# Prova01.net
KiCad netlist of a schematic drawn in EAGLE
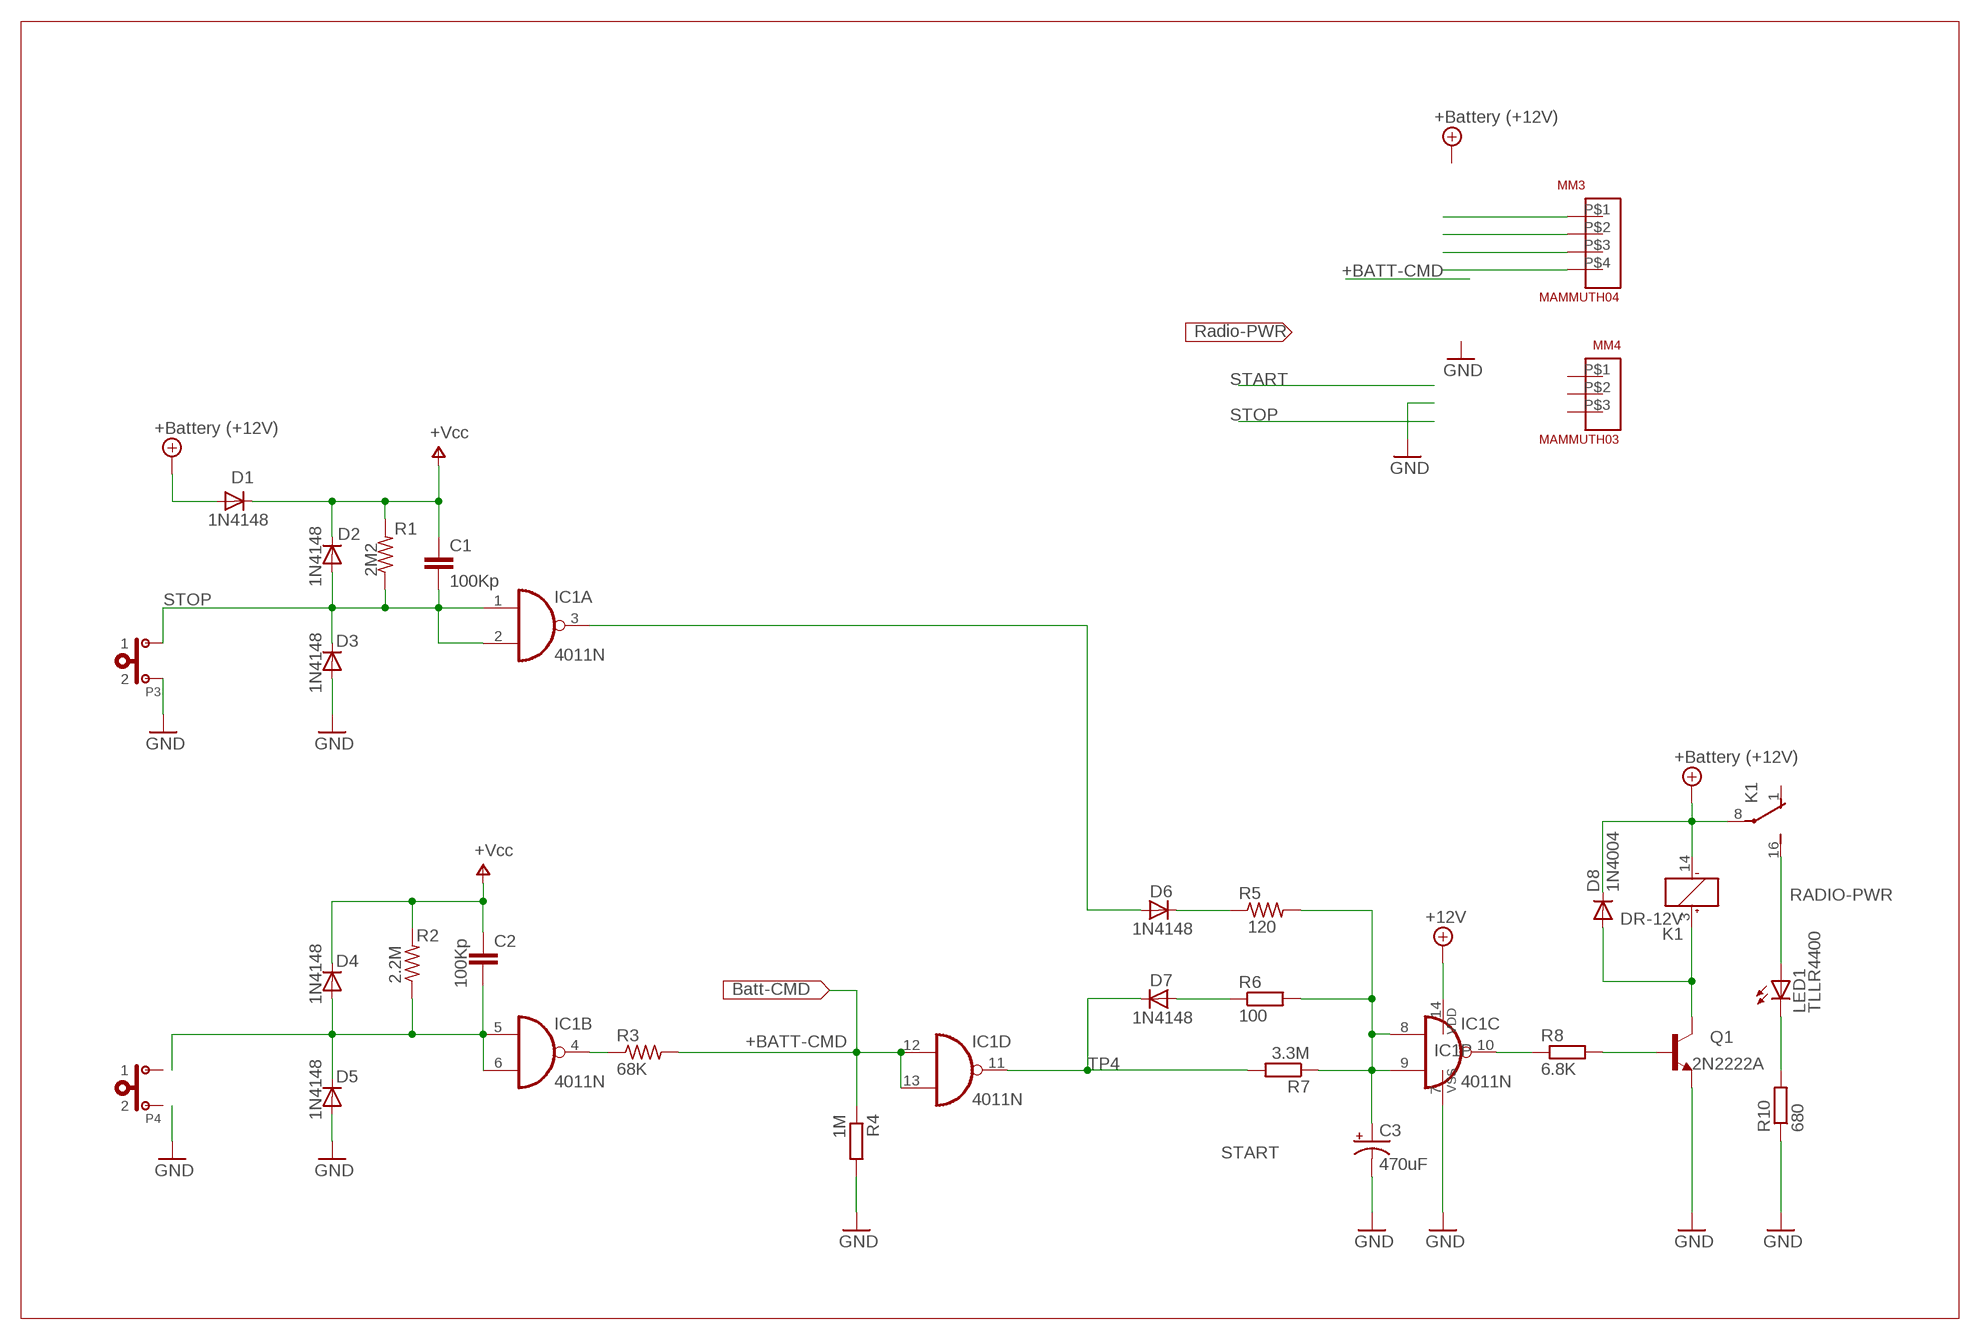
[diagram p0: schematic, sheet 1]

(export (version "E")
  (design (tool "Eeschema 10.0.6"))
  (components
    (comp (ref "C1")
      (value "100Kp")
      (footprint "eagle-import:C025-025X050")
      (libsource (lib "eagle-import") (part "C-EU025-025X050"))
    )
    (comp (ref "C2")
      (value "100Kp")
      (footprint "eagle-import:C025-025X050")
      (libsource (lib "eagle-import") (part "C-EU025-025X050"))
    )
    (comp (ref "C3")
      (value "470uF")
      (footprint "eagle-import:E3,5-8")
      (libsource (lib "eagle-import") (part "CPOL-USE3.5-8"))
    )
    (comp (ref "D1")
      (value "1N4148")
      (footprint "eagle-import:DO35-10")
      (libsource (lib "eagle-import") (part "1N4148DO35-10"))
    )
    (comp (ref "D2")
      (value "1N4148")
      (footprint "eagle-import:DO35-10")
      (libsource (lib "eagle-import") (part "1N4148DO35-10"))
    )
    (comp (ref "D3")
      (value "1N4148")
      (footprint "eagle-import:DO35-10")
      (libsource (lib "eagle-import") (part "1N4148DO35-10"))
    )
    (comp (ref "D4")
      (value "1N4148")
      (footprint "eagle-import:DO35-10")
      (libsource (lib "eagle-import") (part "1N4148DO35-10"))
    )
    (comp (ref "D5")
      (value "1N4148")
      (footprint "eagle-import:DO35-10")
      (libsource (lib "eagle-import") (part "1N4148DO35-10"))
    )
    (comp (ref "D6")
      (value "1N4148")
      (footprint "eagle-import:DO35-10")
      (libsource (lib "eagle-import") (part "1N4148DO35-10"))
    )
    (comp (ref "D7")
      (value "1N4148")
      (footprint "eagle-import:DO35-10")
      (libsource (lib "eagle-import") (part "1N4148DO35-10"))
    )
    (comp (ref "D8")
      (value "1N4004")
      (footprint "eagle-import:DO41-10")
      (libsource (lib "eagle-import") (part "1N4004"))
    )
    (comp (ref "IC1")
      (value "4011N")
      (footprint "eagle-import:DIL14")
      (libsource (lib "eagle-import") (part "4011N"))
    )
    (comp (ref "K1")
      (value "DR-12V")
      (footprint "eagle-import:DR-1")
      (libsource (lib "eagle-import") (part "DR-V12"))
    )
    (comp (ref "LED1")
      (value "TLLR4400")
      (footprint "eagle-import:LED3MM")
      (fields (field (name "MF") "VISHAY SEMICONDUCTOR"))
      (libsource (lib "eagle-import") (part "TLLR4400"))
    )
    (comp (ref "MM3")
      (value "MAMMUTH04")
      (footprint "eagle-import:MAMMUTH04")
      (libsource (lib "eagle-import") (part "MAMMUTH04"))
    )
    (comp (ref "MM4")
      (value "MAMMUTH03")
      (footprint "eagle-import:MAMMUTH03")
      (libsource (lib "eagle-import") (part "MAMMUTH03"))
    )
    (comp (ref "P3")
      (value "PULSANTENO")
      (footprint "eagle-import:SIP02")
      (libsource (lib "eagle-import") (part "PULSANTENO"))
    )
    (comp (ref "P4")
      (value "PULSANTENO")
      (footprint "eagle-import:SIP02")
      (libsource (lib "eagle-import") (part "PULSANTENO"))
    )
    (comp (ref "Q1")
      (value "2N2222A")
      (footprint "eagle-import:TO18")
      (libsource (lib "eagle-import") (part "2N2222A"))
    )
    (comp (ref "R1")
      (value "2M2")
      (footprint "eagle-import:0207_12")
      (libsource (lib "eagle-import") (part "R-US_0207/12"))
    )
    (comp (ref "R2")
      (value "2.2M")
      (footprint "eagle-import:0207_12")
      (libsource (lib "eagle-import") (part "R-US_0207/12"))
    )
    (comp (ref "R3")
      (value "68K")
      (footprint "eagle-import:0207_12")
      (libsource (lib "eagle-import") (part "R-US_0207/12"))
    )
    (comp (ref "R4")
      (value "1M")
      (footprint "eagle-import:0207_10")
      (libsource (lib "eagle-import") (part "R-EU_0207/10"))
    )
    (comp (ref "R5")
      (value "120")
      (footprint "eagle-import:0207_12")
      (libsource (lib "eagle-import") (part "R-US_0207/12"))
    )
    (comp (ref "R6")
      (value "100")
      (footprint "eagle-import:0207_10")
      (libsource (lib "eagle-import") (part "R-EU_0207/10"))
    )
    (comp (ref "R7")
      (value "3.3M")
      (footprint "eagle-import:0207_10")
      (libsource (lib "eagle-import") (part "R-EU_0207/10"))
    )
    (comp (ref "R8")
      (value "6.8K")
      (footprint "eagle-import:0207_10")
      (libsource (lib "eagle-import") (part "R-EU_0207/10"))
    )
    (comp (ref "R10")
      (value "680")
      (footprint "eagle-import:0207_10")
      (libsource (lib "eagle-import") (part "R-EU_0207/10"))
    )
  )
  (nets
    (net (code "1") (name "+12V") (class "Default")
      (node (ref "D1") (pin "A") (pinfunction "A_A") (pintype "passive"))
      (node (ref "D8") (pin "C") (pinfunction "C_C") (pintype "passive"))
      (node (ref "IC1") (pin "14") (pinfunction "VDD_14") (pintype "power_in"))
      (node (ref "K1") (pin "14") (pinfunction "-_14") (pintype "passive"))
      (node (ref "K1") (pin "8") (pinfunction "P_8") (pintype "passive"))
    )
    (net (code "2") (name "+Vcc") (class "Default")
      (node (ref "C1") (pin "1") (pinfunction "1_1") (pintype "passive"))
      (node (ref "C2") (pin "1") (pinfunction "1_1") (pintype "passive"))
      (node (ref "D1") (pin "C") (pinfunction "C_C") (pintype "passive"))
      (node (ref "D2") (pin "C") (pinfunction "C_C") (pintype "passive"))
      (node (ref "D4") (pin "C") (pinfunction "C_C") (pintype "passive"))
      (node (ref "R1") (pin "2") (pinfunction "2_2") (pintype "passive"))
      (node (ref "R2") (pin "2") (pinfunction "2_2") (pintype "passive"))
    )
    (net (code "3") (name "/+BATT-CMD") (class "Default")
      (node (ref "IC1") (pin "12") (pinfunction "I0_12") (pintype "input"))
      (node (ref "IC1") (pin "13") (pinfunction "I1_13") (pintype "input"))
      (node (ref "R3") (pin "2") (pinfunction "2_2") (pintype "passive"))
      (node (ref "R4") (pin "1") (pinfunction "1_1") (pintype "passive"))
    )
    (net (code "4") (name "/RADIO-PWR") (class "Default")
      (node (ref "K1") (pin "16") (pinfunction "S_16") (pintype "passive"))
      (node (ref "LED1") (pin "A") (pinfunction "A_A") (pintype "passive"))
    )
    (net (code "5") (name "/START") (class "Default")
      (node (ref "D7") (pin "A") (pinfunction "A_A") (pintype "passive"))
      (node (ref "R6") (pin "1") (pinfunction "1_1") (pintype "passive"))
    )
    (net (code "6") (name "/STOP") (class "Default")
      (node (ref "C1") (pin "2") (pinfunction "2_2") (pintype "passive"))
      (node (ref "D2") (pin "A") (pinfunction "A_A") (pintype "passive"))
      (node (ref "D3") (pin "C") (pinfunction "C_C") (pintype "passive"))
      (node (ref "IC1") (pin "1") (pinfunction "I0_1") (pintype "input"))
      (node (ref "IC1") (pin "2") (pinfunction "I1_2") (pintype "input"))
      (node (ref "P3") (pin "1") (pinfunction "1_1") (pintype "bidirectional"))
      (node (ref "R1") (pin "1") (pinfunction "1_1") (pintype "passive"))
    )
    (net (code "7") (name "/TP4") (class "Default")
      (node (ref "D7") (pin "C") (pinfunction "C_C") (pintype "passive"))
      (node (ref "IC1") (pin "11") (pinfunction "O_11") (pintype "output"))
      (node (ref "R7") (pin "2") (pinfunction "2_2") (pintype "passive"))
    )
    (net (code "8") (name "GND") (class "Default")
      (node (ref "C3") (pin "-") (pinfunction "-_-") (pintype "passive"))
      (node (ref "D3") (pin "A") (pinfunction "A_A") (pintype "passive"))
      (node (ref "D5") (pin "A") (pinfunction "A_A") (pintype "passive"))
      (node (ref "IC1") (pin "7") (pinfunction "VSS_7") (pintype "power_in"))
      (node (ref "P3") (pin "2") (pinfunction "2_2") (pintype "bidirectional"))
      (node (ref "Q1") (pin "1") (pinfunction "E_1") (pintype "passive"))
      (node (ref "R10") (pin "1") (pinfunction "1_1") (pintype "passive"))
      (node (ref "R4") (pin "2") (pinfunction "2_2") (pintype "passive"))
    )
    (net (code "9") (name "Net-(D6-PadC)") (class "Default")
      (node (ref "D6") (pin "C") (pinfunction "C_C") (pintype "passive"))
      (node (ref "R5") (pin "1") (pinfunction "1_1") (pintype "passive"))
    )
    (net (code "10") (name "Net-(IC1A-O)") (class "Default")
      (node (ref "D6") (pin "A") (pinfunction "A_A") (pintype "passive"))
      (node (ref "IC1") (pin "3") (pinfunction "O_3") (pintype "output"))
    )
    (net (code "11") (name "Net-(IC1B-I0)") (class "Default")
      (node (ref "C2") (pin "2") (pinfunction "2_2") (pintype "passive"))
      (node (ref "D4") (pin "A") (pinfunction "A_A") (pintype "passive"))
      (node (ref "D5") (pin "C") (pinfunction "C_C") (pintype "passive"))
      (node (ref "IC1") (pin "5") (pinfunction "I0_5") (pintype "input"))
      (node (ref "IC1") (pin "6") (pinfunction "I1_6") (pintype "input"))
      (node (ref "R2") (pin "1") (pinfunction "1_1") (pintype "passive"))
    )
    (net (code "12") (name "Net-(IC1B-O)") (class "Default")
      (node (ref "IC1") (pin "4") (pinfunction "O_4") (pintype "output"))
      (node (ref "R3") (pin "1") (pinfunction "1_1") (pintype "passive"))
    )
    (net (code "13") (name "Net-(IC1C-I0)") (class "Default")
      (node (ref "C3") (pin "+") (pinfunction "+_+") (pintype "passive"))
      (node (ref "IC1") (pin "8") (pinfunction "I0_8") (pintype "input"))
      (node (ref "IC1") (pin "9") (pinfunction "I1_9") (pintype "input"))
      (node (ref "R5") (pin "2") (pinfunction "2_2") (pintype "passive"))
      (node (ref "R6") (pin "2") (pinfunction "2_2") (pintype "passive"))
      (node (ref "R7") (pin "1") (pinfunction "1_1") (pintype "passive"))
    )
    (net (code "14") (name "Net-(IC1C-O)") (class "Default")
      (node (ref "IC1") (pin "10") (pinfunction "O_10") (pintype "output"))
      (node (ref "R8") (pin "1") (pinfunction "1_1") (pintype "passive"))
    )
    (net (code "15") (name "Net-(K1A-+)") (class "Default")
      (node (ref "D8") (pin "A") (pinfunction "A_A") (pintype "passive"))
      (node (ref "K1") (pin "3") (pinfunction "+_3") (pintype "passive"))
      (node (ref "Q1") (pin "3") (pinfunction "C_3") (pintype "passive"))
    )
    (net (code "16") (name "Net-(LED1-C)") (class "Default")
      (node (ref "LED1") (pin "K") (pinfunction "C_K") (pintype "passive"))
      (node (ref "R10") (pin "2") (pinfunction "2_2") (pintype "passive"))
    )
    (net (code "17") (name "Net-(Q1-B)") (class "Default")
      (node (ref "Q1") (pin "2") (pinfunction "B_2") (pintype "passive"))
      (node (ref "R8") (pin "2") (pinfunction "2_2") (pintype "passive"))
    )
    (net (code "18") (name "unconnected-(K1B-O-Pad1)") (class "Default")
      (node (ref "K1") (pin "1") (pinfunction "O_1") (pintype "passive"))
    )
    (net (code "19") (name "unconnected-(MM3-PadP$1)") (class "Default")
      (node (ref "MM3") (pin "P$1") (pinfunction "P$1_P$1") (pintype "bidirectional"))
    )
    (net (code "20") (name "unconnected-(MM3-PadP$2)") (class "Default")
      (node (ref "MM3") (pin "P$2") (pinfunction "P$2_P$2") (pintype "bidirectional"))
    )
    (net (code "21") (name "unconnected-(MM3-PadP$3)") (class "Default")
      (node (ref "MM3") (pin "P$3") (pinfunction "P$3_P$3") (pintype "bidirectional"))
    )
    (net (code "22") (name "unconnected-(MM3-PadP$4)") (class "Default")
      (node (ref "MM3") (pin "P$4") (pinfunction "P$4_P$4") (pintype "bidirectional"))
    )
    (net (code "23") (name "unconnected-(MM4-PadP$1)") (class "Default")
      (node (ref "MM4") (pin "P$1") (pinfunction "P$1_P$1") (pintype "bidirectional"))
    )
    (net (code "24") (name "unconnected-(MM4-PadP$2)") (class "Default")
      (node (ref "MM4") (pin "P$2") (pinfunction "P$2_P$2") (pintype "bidirectional"))
    )
    (net (code "25") (name "unconnected-(MM4-PadP$3)") (class "Default")
      (node (ref "MM4") (pin "P$3") (pinfunction "P$3_P$3") (pintype "bidirectional"))
    )
    (net (code "26") (name "unconnected-(P4-Pad1)") (class "Default")
      (node (ref "P4") (pin "1") (pinfunction "1_1") (pintype "bidirectional"))
    )
    (net (code "27") (name "unconnected-(P4-Pad2)") (class "Default")
      (node (ref "P4") (pin "2") (pinfunction "2_2") (pintype "bidirectional"))
    )
  )
)
